# Heater_Power.net
KiCad netlist of a schematic drawn in Altium Designer
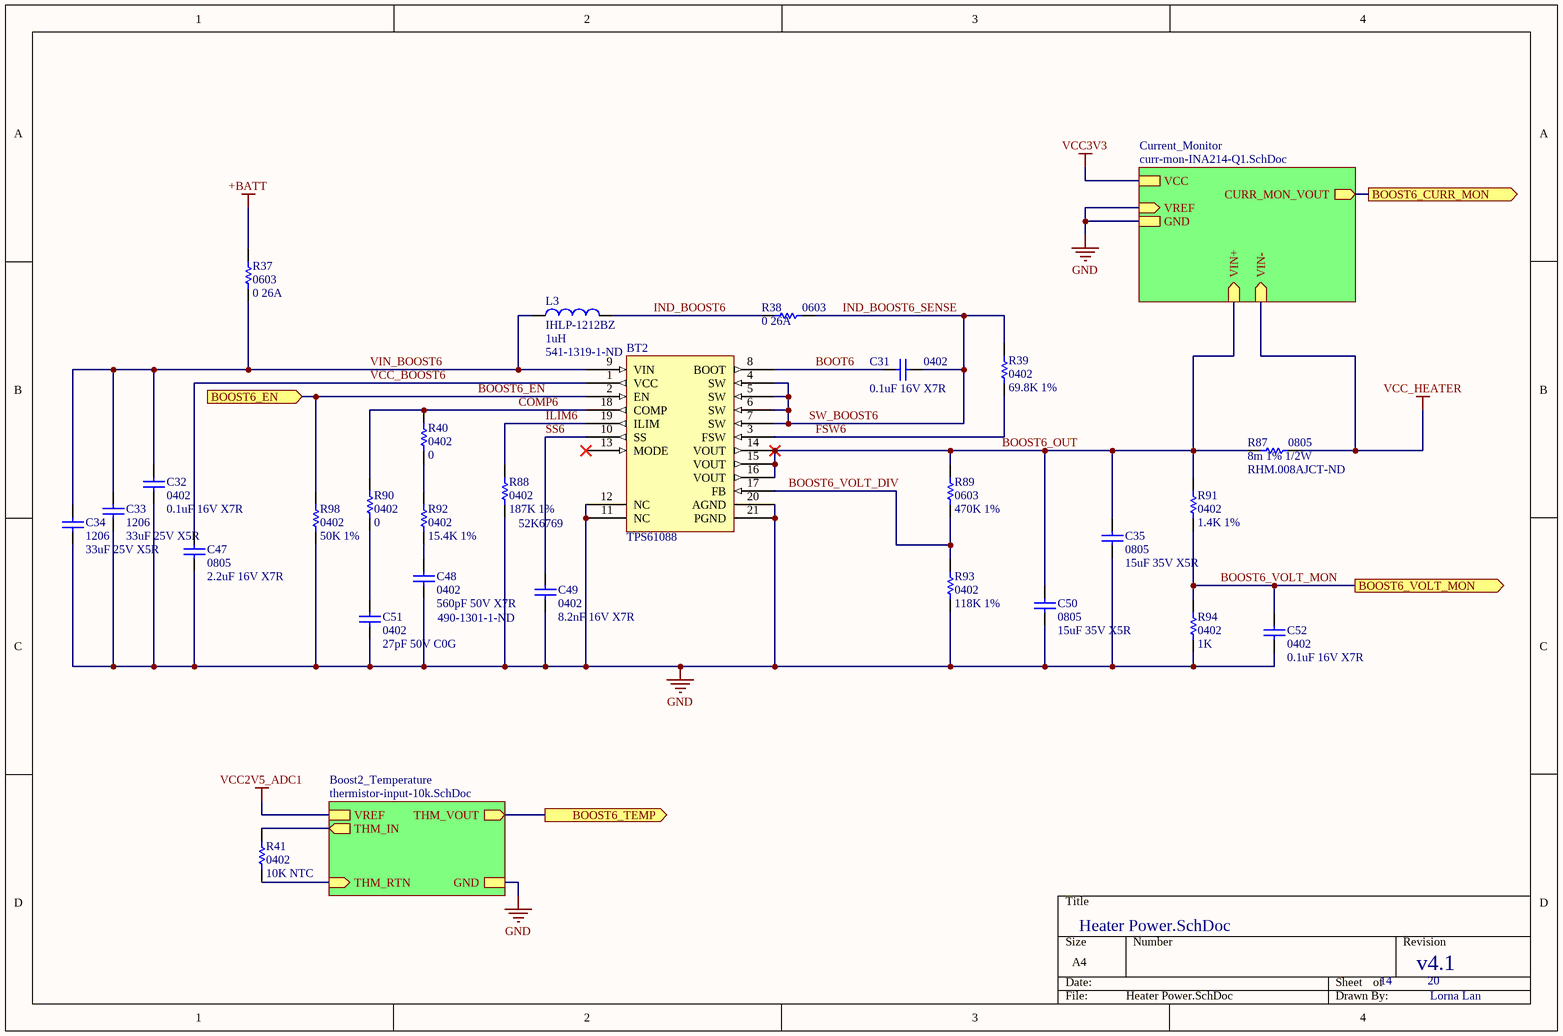
[diagram p0: Heater Power.SchDoc]

(export (version "E")
  (design (tool "Eeschema 10.0.6"))
  (components
    (comp (ref "BT2")
      (value "TPS61088")
      (footprint "QFN50P450X350X100-21N")
      (description "Boost converter")
      (libsource (lib "EPS") (part "TPS61088"))
    )
    (comp (ref "C31")
      (value "0402")
      (footprint "CAP0402R")
      (description "0402 capacitor")
      (fields (field (name "ALTIUM_VALUE") "0.1uF 16V X7R"))
      (libsource (lib "heron-general") (part "CAP0402"))
    )
    (comp (ref "C32")
      (value "0402")
      (footprint "CAP0402R")
      (description "0402 capacitor")
      (fields (field (name "ALTIUM_VALUE") "0.1uF 16V X7R"))
      (libsource (lib "heron-general") (part "CAP0402"))
    )
    (comp (ref "C33")
      (value "1206")
      (footprint "CAP1206R")
      (description "1206 capacitor")
      (fields (field (name "ALTIUM_VALUE") "33uF 25V X5R"))
      (libsource (lib "heron-general") (part "CAP1206"))
    )
    (comp (ref "C34")
      (value "1206")
      (footprint "CAP1206R")
      (description "1206 capacitor")
      (fields (field (name "ALTIUM_VALUE") "33uF 25V X5R"))
      (libsource (lib "heron-general") (part "CAP1206"))
    )
    (comp (ref "C35")
      (value "0805")
      (footprint "CAP0805R")
      (description "0805 capacitor")
      (fields (field (name "ALTIUM_VALUE") "15uF 35V X5R"))
      (libsource (lib "heron-general") (part "CAP0805"))
    )
    (comp (ref "C47")
      (value "0805")
      (footprint "CAP0805R")
      (description "0805 capacitor")
      (fields (field (name "ALTIUM_VALUE") "2.2uF 16V X7R"))
      (libsource (lib "heron-general") (part "CAP0805"))
    )
    (comp (ref "C48")
      (value "0402")
      (footprint "CAP0402R")
      (description "0402 capacitor")
      (fields
        (field (name "ALTIUM_VALUE") "560pF 50V X7R")
        (field (name "SUPPLIER PART NUMBER 1") "490-1301-1-ND")
      )
      (libsource (lib "heron-general") (part "CAP0402"))
    )
    (comp (ref "C49")
      (value "0402")
      (footprint "CAP0402R")
      (description "0402 capacitor")
      (fields (field (name "ALTIUM_VALUE") "8.2nF 16V X7R"))
      (libsource (lib "CAP0402") (part "CAP0402"))
    )
    (comp (ref "C50")
      (value "0805")
      (footprint "CAP0805R")
      (description "0805 capacitor")
      (fields (field (name "ALTIUM_VALUE") "15uF 35V X5R"))
      (libsource (lib "heron-general") (part "CAP0805"))
    )
    (comp (ref "C51")
      (value "0402")
      (footprint "CAP0402R")
      (description "0402 capacitor")
      (fields (field (name "ALTIUM_VALUE") "27pF 50V C0G"))
      (libsource (lib "heron-general") (part "CAP0402"))
    )
    (comp (ref "C52")
      (value "0402")
      (footprint "CAP0402R")
      (description "0402 capacitor")
      (fields (field (name "ALTIUM_VALUE") "0.1uF 16V X7R"))
      (libsource (lib "heron-general") (part "CAP0402"))
    )
    (comp (ref "L3")
      (value "IHLP-1212BZ")
      (footprint "IHLP-1212BZ")
      (description "1µH Shielded Molded Inductor 5A 24mOhm Max Nonstandard")
      (fields
        (field (name "MANUFACTURER") "Vishay Dale")
        (field (name "MANUFACTURER PART NUMBER") "IHLP1212BZER1R0M11")
        (field (name "INDUCTANCE") "1uH")
        (field (name "SUPPLIER PART NUMBER 1") "541-1319-1-ND")
      )
      (libsource (lib "heron-general") (part "IND_IHLP-1212BZ"))
    )
    (comp (ref "R37")
      (value "0603")
      (footprint "RES0603R")
      (description "0603 resistor")
      (fields (field (name "ALTIUM_VALUE") "0 26A"))
      (libsource (lib "heron-general") (part "RES0603"))
    )
    (comp (ref "R38")
      (value "0603")
      (footprint "RES0603R")
      (description "0603 resistor")
      (fields (field (name "ALTIUM_VALUE") "0 26A"))
      (libsource (lib "heron-general") (part "RES0603"))
    )
    (comp (ref "R39")
      (value "0402")
      (footprint "RES0402R")
      (description "0402 resistor")
      (fields (field (name "ALTIUM_VALUE") "69.8K 1%"))
      (libsource (lib "heron-general") (part "RES0402"))
    )
    (comp (ref "R40")
      (value "0402")
      (footprint "RES0402R")
      (description "0402 resistor")
      (fields
        (field (name "ALTIUM_VALUE") "0")
        (field (name "MANUFACTURER") "Panasonic")
        (field (name "MANUFACTURER PART NUMBER") "ERJ-2GE0R00X")
      )
      (libsource (lib "heron-general") (part "RES0402"))
    )
    (comp (ref "R41")
      (value "0402")
      (footprint "RES0402R")
      (description "0402 resistor")
      (fields (field (name "ALTIUM_VALUE") "10K NTC"))
      (libsource (lib "heron-general") (part "RES0402"))
    )
    (comp (ref "R87")
      (value "0805")
      (footprint "RES0805R")
      (description "0805 resistor")
      (fields
        (field (name "ALTIUM_VALUE") "8m 1% 1/2W")
        (field (name "SUPPLIER PART NUMBER 1") "RHM.008AJCT-ND")
      )
      (libsource (lib "RES0805") (part "RES0805"))
    )
    (comp (ref "R88")
      (value "0402")
      (footprint "RES0402R")
      (description "0402 resistor")
      (fields (field (name "ALTIUM_VALUE") "187K 1%") (field (name "SUPPLIER PART NUMBER 1") "52K6769"))
      (libsource (lib "heron-general") (part "RES0402"))
    )
    (comp (ref "R89")
      (value "0603")
      (footprint "RES0603R")
      (description "0603 resistor")
      (fields (field (name "ALTIUM_VALUE") "470K 1%"))
      (libsource (lib "RES0603") (part "RES0603"))
    )
    (comp (ref "R90")
      (value "0402")
      (footprint "RES0402R")
      (description "0402 resistor")
      (fields
        (field (name "ALTIUM_VALUE") "0")
        (field (name "MANUFACTURER") "Panasonic")
        (field (name "MANUFACTURER PART NUMBER") "ERJ-2GE0R00X")
      )
      (libsource (lib "heron-general") (part "RES0402"))
    )
    (comp (ref "R91")
      (value "0402")
      (footprint "RES0402R")
      (description "0402 resistor")
      (fields (field (name "ALTIUM_VALUE") "1.4K 1%"))
      (libsource (lib "RES0402") (part "RES0402"))
    )
    (comp (ref "R92")
      (value "0402")
      (footprint "RES0402R")
      (description "0402 resistor")
      (fields (field (name "ALTIUM_VALUE") "15.4K 1%"))
      (libsource (lib "heron-general") (part "RES0402"))
    )
    (comp (ref "R93")
      (value "0402")
      (footprint "RES0402R")
      (description "0402 resistor")
      (fields (field (name "ALTIUM_VALUE") "118K 1%"))
      (libsource (lib "RES0402") (part "RES0402"))
    )
    (comp (ref "R94")
      (value "0402")
      (footprint "RES0402R")
      (description "0402 resistor")
      (fields (field (name "ALTIUM_VALUE") "1K"))
      (libsource (lib "RES0402") (part "RES0402"))
    )
    (comp (ref "R98")
      (value "0402")
      (footprint "RES0402R")
      (description "0402 resistor")
      (fields (field (name "ALTIUM_VALUE") "50K 1%"))
      (libsource (lib "heron-general") (part "RES0402"))
    )
  )
  (nets
    (net (code "1") (name "+BATT") (class "Default")
      (node (ref "R37") (pin "2") (pinfunction "2_2") (pintype "passive"))
    )
    (net (code "3") (name "/BOOST6_EN") (class "Default")
      (node (ref "BT2") (pin "2") (pinfunction "EN_2") (pintype "input"))
      (node (ref "R98") (pin "2") (pinfunction "2_2") (pintype "passive"))
    )
    (net (code "4") (name "/BOOST6_OUT") (class "Default")
      (node (ref "BT2") (pin "14") (pinfunction "VOUT_14") (pintype "output"))
      (node (ref "BT2") (pin "15") (pinfunction "VOUT_15") (pintype "output"))
      (node (ref "BT2") (pin "16") (pinfunction "VOUT_16") (pintype "output"))
      (node (ref "C35") (pin "2") (pinfunction "2_2") (pintype "passive"))
      (node (ref "C50") (pin "2") (pinfunction "2_2") (pintype "passive"))
      (node (ref "R87") (pin "1") (pinfunction "1_1") (pintype "passive"))
      (node (ref "R89") (pin "2") (pinfunction "2_2") (pintype "passive"))
      (node (ref "R91") (pin "2") (pinfunction "2_2") (pintype "passive"))
    )
    (net (code "6") (name "/BOOST6_VOLT_DIV") (class "Default")
      (node (ref "BT2") (pin "17") (pinfunction "FB_17") (pintype "input"))
      (node (ref "R89") (pin "1") (pinfunction "1_1") (pintype "passive"))
      (node (ref "R93") (pin "2") (pinfunction "2_2") (pintype "passive"))
    )
    (net (code "7") (name "/BOOST6_VOLT_MON") (class "Default")
      (node (ref "C52") (pin "2") (pinfunction "2_2") (pintype "passive"))
      (node (ref "R91") (pin "1") (pinfunction "1_1") (pintype "passive"))
      (node (ref "R94") (pin "2") (pinfunction "2_2") (pintype "passive"))
    )
    (net (code "8") (name "/BOOT6") (class "Default")
      (node (ref "BT2") (pin "8") (pinfunction "BOOT_8") (pintype "output"))
      (node (ref "C31") (pin "1") (pinfunction "1_1") (pintype "passive"))
    )
    (net (code "9") (name "/COMP6") (class "Default")
      (node (ref "BT2") (pin "18") (pinfunction "COMP_18") (pintype "output"))
      (node (ref "R40") (pin "2") (pinfunction "2_2") (pintype "passive"))
      (node (ref "R90") (pin "2") (pinfunction "2_2") (pintype "passive"))
    )
    (net (code "10") (name "/FSW6") (class "Default")
      (node (ref "BT2") (pin "3") (pinfunction "FSW_3") (pintype "input"))
      (node (ref "R39") (pin "1") (pinfunction "1_1") (pintype "passive"))
    )
    (net (code "11") (name "/ILIM6") (class "Default")
      (node (ref "BT2") (pin "19") (pinfunction "ILIM_19") (pintype "output"))
      (node (ref "R88") (pin "2") (pinfunction "2_2") (pintype "passive"))
    )
    (net (code "12") (name "/IND_BOOST6") (class "Default")
      (node (ref "L3") (pin "2") (pinfunction "2_2") (pintype "passive"))
      (node (ref "R38") (pin "1") (pinfunction "1_1") (pintype "passive"))
    )
    (net (code "13") (name "/IND_BOOST6_SENSE") (class "Default")
      (node (ref "BT2") (pin "4") (pinfunction "SW_4") (pintype "input"))
      (node (ref "BT2") (pin "5") (pinfunction "SW_5") (pintype "input"))
      (node (ref "BT2") (pin "6") (pinfunction "SW_6") (pintype "input"))
      (node (ref "BT2") (pin "7") (pinfunction "SW_7") (pintype "input"))
      (node (ref "C31") (pin "2") (pinfunction "2_2") (pintype "passive"))
      (node (ref "R38") (pin "2") (pinfunction "2_2") (pintype "passive"))
      (node (ref "R39") (pin "2") (pinfunction "2_2") (pintype "passive"))
    )
    (net (code "14") (name "/SS6") (class "Default")
      (node (ref "BT2") (pin "10") (pinfunction "SS_10") (pintype "output"))
      (node (ref "C49") (pin "2") (pinfunction "2_2") (pintype "passive"))
    )
    (net (code "15") (name "/THM_IN") (class "Default")
      (node (ref "R41") (pin "2") (pinfunction "2_2") (pintype "passive"))
    )
    (net (code "16") (name "/THM_RTN") (class "Default")
      (node (ref "R41") (pin "1") (pinfunction "1_1") (pintype "passive"))
    )
    (net (code "17") (name "/VCC_BOOST6") (class "Default")
      (node (ref "BT2") (pin "1") (pinfunction "VCC_1") (pintype "output"))
      (node (ref "C47") (pin "2") (pinfunction "2_2") (pintype "passive"))
    )
    (net (code "18") (name "/VIN_BOOST6") (class "Default")
      (node (ref "BT2") (pin "9") (pinfunction "VIN_9") (pintype "input"))
      (node (ref "C32") (pin "2") (pinfunction "2_2") (pintype "passive"))
      (node (ref "C33") (pin "2") (pinfunction "2_2") (pintype "passive"))
      (node (ref "C34") (pin "2") (pinfunction "2_2") (pintype "passive"))
      (node (ref "L3") (pin "1") (pinfunction "1_1") (pintype "passive"))
      (node (ref "R37") (pin "1") (pinfunction "1_1") (pintype "passive"))
    )
    (net (code "19") (name "GND") (class "Default")
      (node (ref "BT2") (pin "11") (pinfunction "NC_11") (pintype "passive"))
      (node (ref "BT2") (pin "12") (pinfunction "NC_12") (pintype "passive"))
      (node (ref "BT2") (pin "20") (pinfunction "AGND_20") (pintype "power_in"))
      (node (ref "BT2") (pin "21") (pinfunction "PGND_21") (pintype "power_in"))
      (node (ref "C32") (pin "1") (pinfunction "1_1") (pintype "passive"))
      (node (ref "C33") (pin "1") (pinfunction "1_1") (pintype "passive"))
      (node (ref "C34") (pin "1") (pinfunction "1_1") (pintype "passive"))
      (node (ref "C35") (pin "1") (pinfunction "1_1") (pintype "passive"))
      (node (ref "C47") (pin "1") (pinfunction "1_1") (pintype "passive"))
      (node (ref "C48") (pin "1") (pinfunction "1_1") (pintype "passive"))
      (node (ref "C49") (pin "1") (pinfunction "1_1") (pintype "passive"))
      (node (ref "C50") (pin "1") (pinfunction "1_1") (pintype "passive"))
      (node (ref "C51") (pin "1") (pinfunction "1_1") (pintype "passive"))
      (node (ref "C52") (pin "1") (pinfunction "1_1") (pintype "passive"))
      (node (ref "R88") (pin "1") (pinfunction "1_1") (pintype "passive"))
      (node (ref "R93") (pin "1") (pinfunction "1_1") (pintype "passive"))
      (node (ref "R94") (pin "1") (pinfunction "1_1") (pintype "passive"))
      (node (ref "R98") (pin "1") (pinfunction "1_1") (pintype "passive"))
    )
    (net (code "20") (name "Net-(C48-Pad2)") (class "Default")
      (node (ref "C48") (pin "2") (pinfunction "2_2") (pintype "passive"))
      (node (ref "R92") (pin "1") (pinfunction "1_1") (pintype "passive"))
    )
    (net (code "21") (name "Net-(C51-Pad2)") (class "Default")
      (node (ref "C51") (pin "2") (pinfunction "2_2") (pintype "passive"))
      (node (ref "R90") (pin "1") (pinfunction "1_1") (pintype "passive"))
    )
    (net (code "22") (name "Net-(R40-Pad1)") (class "Default")
      (node (ref "R40") (pin "1") (pinfunction "1_1") (pintype "passive"))
      (node (ref "R92") (pin "2") (pinfunction "2_2") (pintype "passive"))
    )
    (net (code "25") (name "VCC_HEATER") (class "Default")
      (node (ref "R87") (pin "2") (pinfunction "2_2") (pintype "passive"))
    )
    (net (code "26") (name "unconnected-(BT2-MODE-Pad13)") (class "Default")
      (node (ref "BT2") (pin "13") (pinfunction "MODE_13") (pintype "input+no_connect"))
    )
  )
)
